# Sheet2.net
KiCad netlist of a schematic drawn in Altium Designer
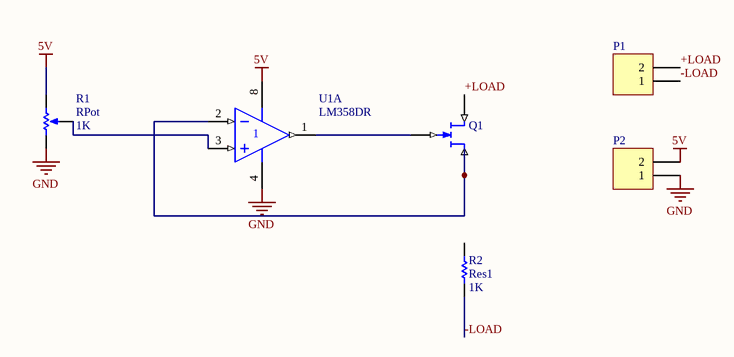
[diagram p0: Sheet2.SchDoc]

(export (version "E")
  (design (tool "Eeschema 10.0.6"))
  (components
    (comp (ref "P1")
      (value "Header 2")
      (footprint "HDR1X2")
      (description "Header, 2-Pin")
      (fields (field (name "PUBLISHER") "Altium Limited"))
      (libsource (lib "Miscellaneous Connectors") (part "Header 2"))
    )
    (comp (ref "P2")
      (value "Header 2")
      (footprint "HDR1X2")
      (description "Header, 2-Pin")
      (fields (field (name "PUBLISHER") "Altium Limited"))
      (libsource (lib "Miscellaneous Connectors") (part "Header 2"))
    )
    (comp (ref "Q1")
      (value "MESFET-N")
      (footprint "DPAK228P962X230-3N")
      (description "N-Channel MESFET")
      (fields (field (name "PUBLISHER") "Altium Limited"))
      (libsource (lib "Miscellaneous Devices") (part "MESFET-N"))
    )
    (comp (ref "R1")
      (value "RPot")
      (footprint "Rm065-v1")
      (description "Potentiometer")
      (fields (field (name "ALTIUM_VALUE") "1K") (field (name "PUBLISHER") "Altium Limited"))
      (libsource (lib "Miscellaneous Devices") (part "RPot"))
    )
    (comp (ref "R2")
      (value "Res1")
      (footprint "AXIAL-0.3")
      (description "Resistor")
      (fields (field (name "ALTIUM_VALUE") "1K") (field (name "PUBLISHER") "Altium Limited"))
      (libsource (lib "Miscellaneous Devices") (part "Res1"))
    )
    (comp (ref "U1")
      (value "LM358DR")
      (footprint "D008_L")
      (description "Dual Operational Amplifier")
      (fields (field (name "PUBLISHER") "Altium Limited"))
      (libsource (lib "TI Operational Amplifier") (part "LM358DR"))
    )
  )
  (nets
    (net (code "1") (name "/+LOAD") (class "Default")
      (node (ref "P1") (pin "2") (pinfunction "2_2") (pintype "passive"))
      (node (ref "Q1") (pin "2") (pinfunction "D_2") (pintype "input"))
    )
    (net (code "2") (name "/-LOAD") (class "Default")
      (node (ref "P1") (pin "1") (pinfunction "1_1") (pintype "passive"))
      (node (ref "R2") (pin "1") (pinfunction "1_1") (pintype "passive"))
    )
    (net (code "3") (name "5V") (class "Default")
      (node (ref "P2") (pin "2") (pinfunction "2_2") (pintype "passive"))
      (node (ref "R1") (pin "2") (pinfunction "BOT_2") (pintype "passive"))
      (node (ref "U1") (pin "8") (pinfunction "V+_8") (pintype "power_in"))
    )
    (net (code "4") (name "GND") (class "Default")
      (node (ref "P2") (pin "1") (pinfunction "1_1") (pintype "passive"))
      (node (ref "R1") (pin "1") (pinfunction "TOP_1") (pintype "passive"))
      (node (ref "U1") (pin "4") (pinfunction "V-_4") (pintype "power_in"))
    )
    (net (code "5") (name "Net-(Q1-G)") (class "Default")
      (node (ref "Q1") (pin "1") (pinfunction "G_1") (pintype "input"))
      (node (ref "U1") (pin "1") (pinfunction "OUT_1") (pintype "output"))
    )
    (net (code "6") (name "Net-(Q1-S)") (class "Default")
      (node (ref "Q1") (pin "3") (pinfunction "S_3") (pintype "input"))
      (node (ref "U1") (pin "2") (pinfunction "IN-_2") (pintype "input"))
    )
    (net (code "7") (name "Net-(R1-TAP)") (class "Default")
      (node (ref "R1") (pin "3") (pinfunction "TAP_3") (pintype "passive"))
      (node (ref "U1") (pin "3") (pinfunction "IN+_3") (pintype "input"))
    )
    (net (code "8") (name "unconnected-(R2-Pad2)") (class "Default")
      (node (ref "R2") (pin "2") (pinfunction "2_2") (pintype "passive"))
    )
  )
)
